# 2014_BALISE_CARTE_EMETTEUR.net
KiCad netlist of a schematic drawn in Altium Designer
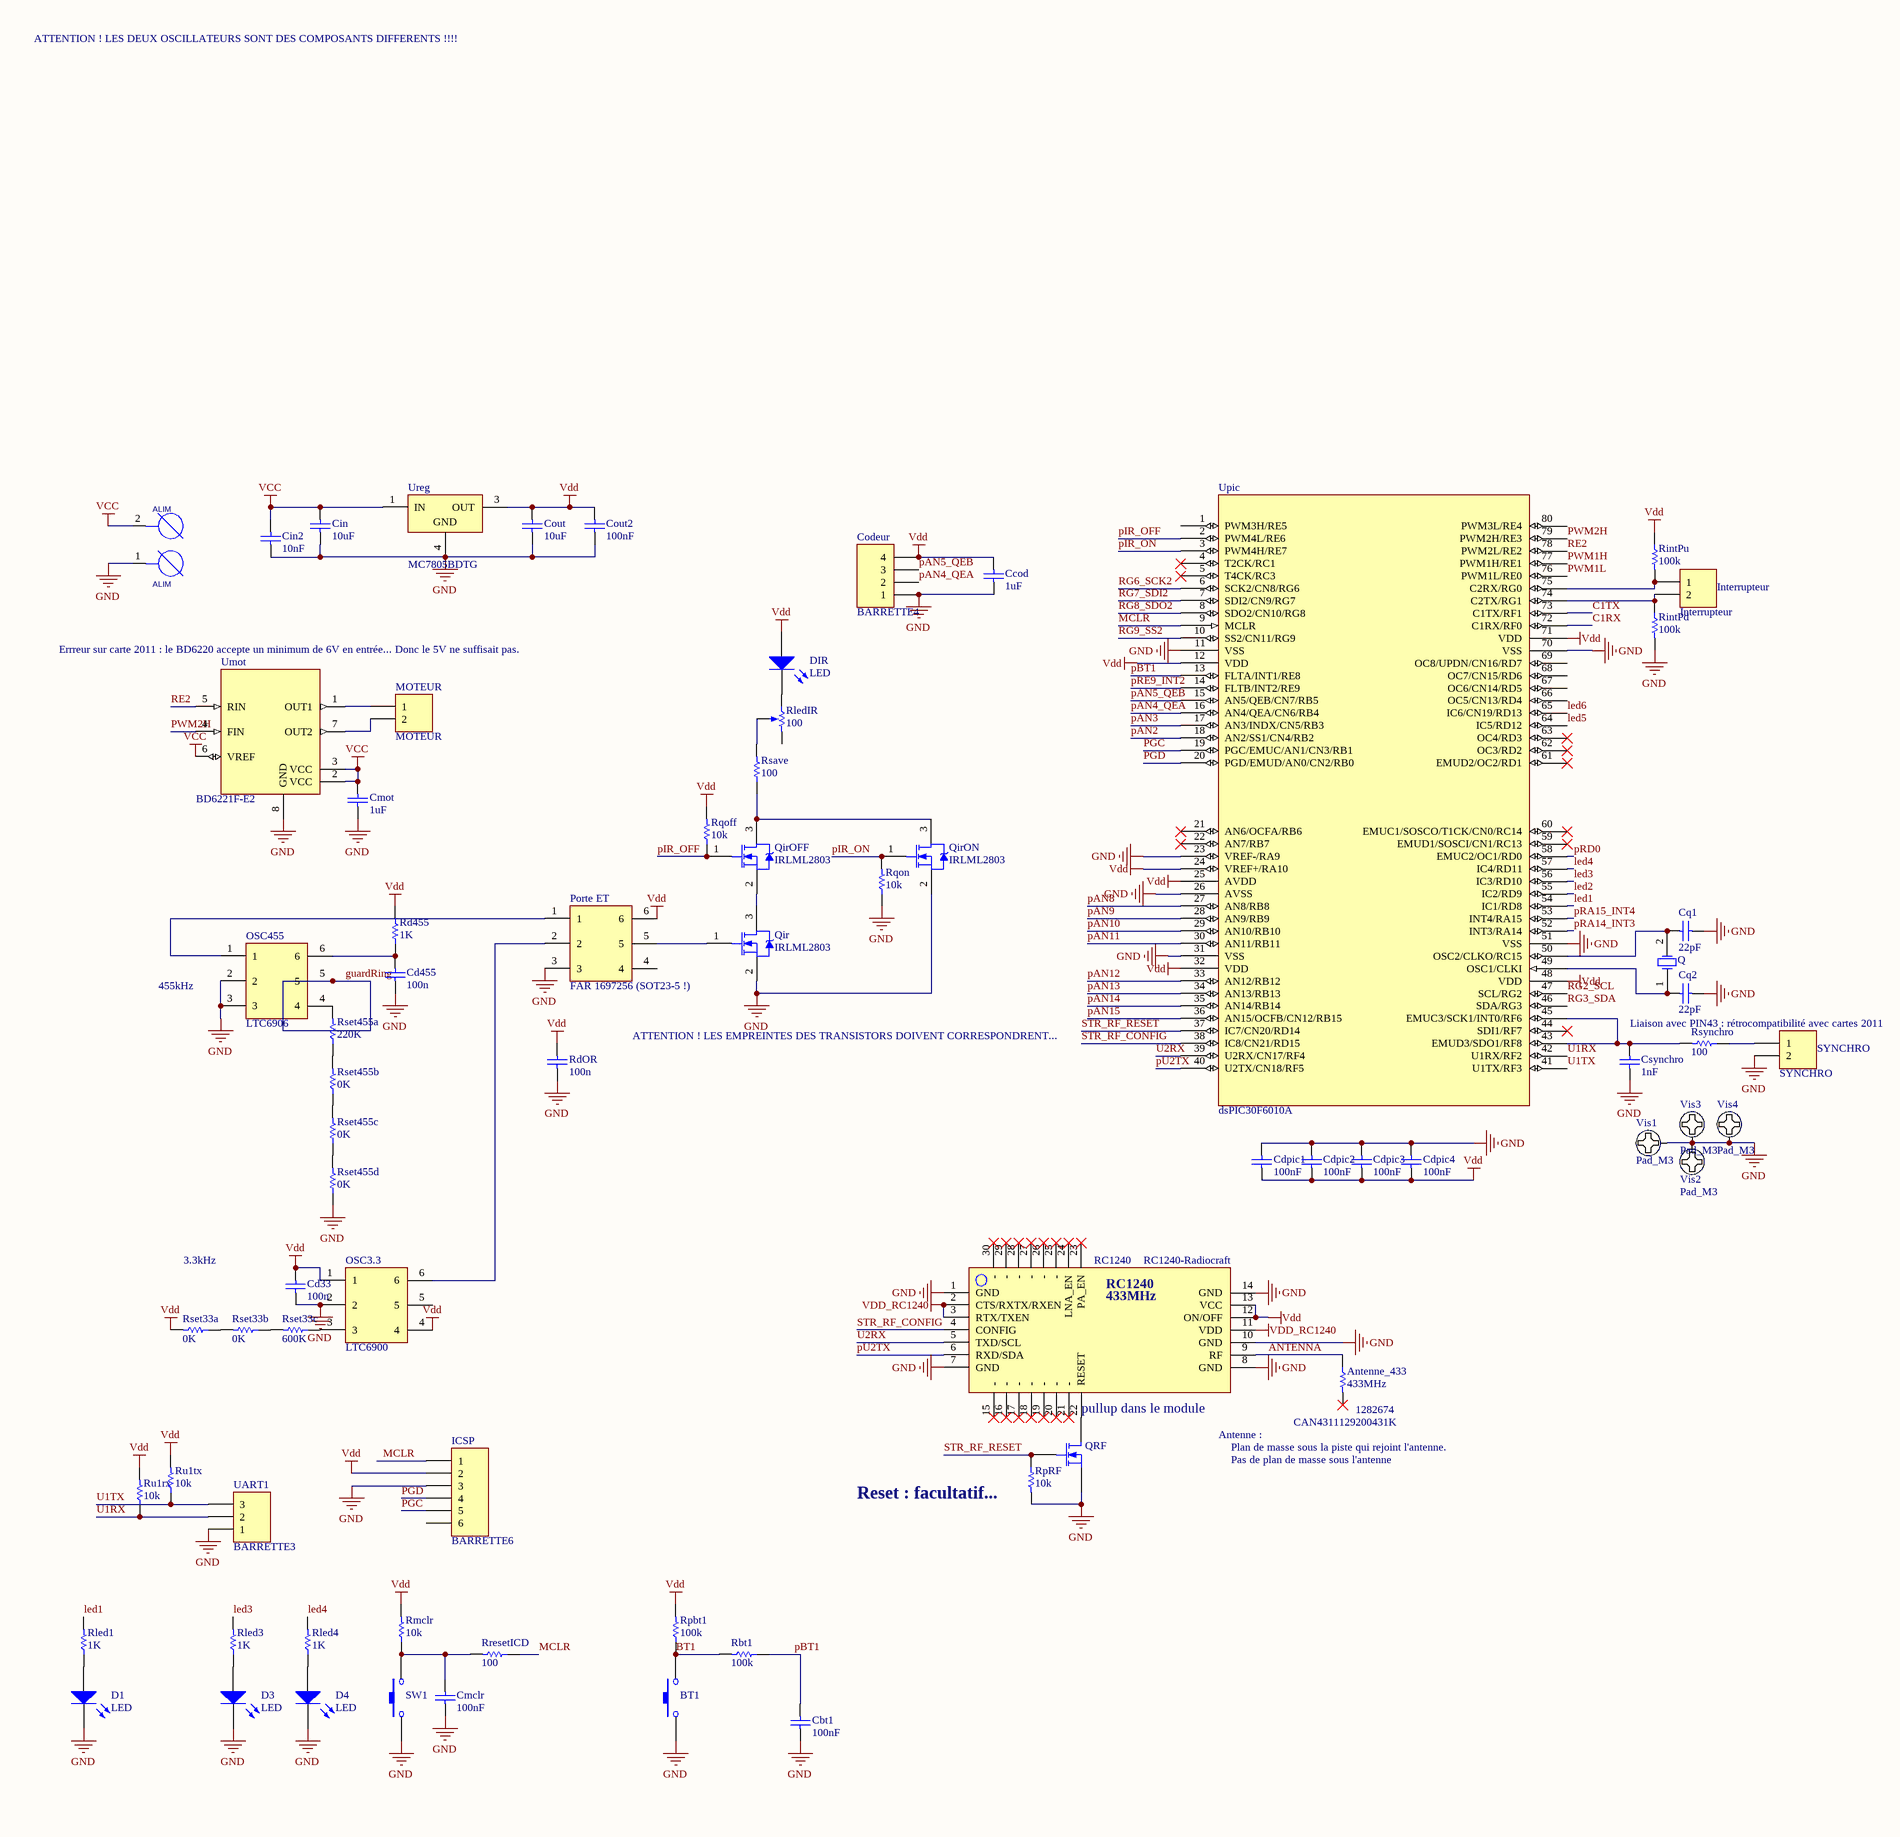
[diagram p0: 2014_BALISE_CARTE_EMETTEUR.SchDoc, left]
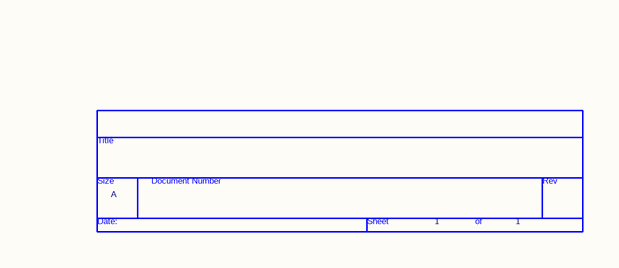
[diagram p1: 2014_BALISE_CARTE_EMETTEUR.SchDoc, right]

(export (version "E")
  (design (tool "Eeschema 10.0.6"))
  (components
    (comp (ref "*")
      (value "TitleBlock0")
      (fields (field (name "PAGE COUNT") "1") (field (name "PAGE NUMBER") "1") (field (name "PAGE SIZE") "A"))
      (libsource (lib "*") (part "TitleBlock0"))
    )
    (comp (ref "ALIM") (value "ALIM") (footprint "BORNIER2") (libsource (lib "*") (part "BORNIER2")))
    (comp (ref "Antenne_433")
      (value "433MHz")
      (footprint "R1206_N")
      (description "CAN4311129200431K")
      (fields
        (field (name "PACKAGEREFERENCE") "CAN4311129200431K")
        (field (name "FAR") "1282674")
        (field (name "PUBLISHER") "Altium Limited")
      )
      (libsource (lib "_ROBOT") (part "Resistor"))
    )
    (comp (ref "BT1")
      (value "SW_Pushbutton_6x6mm_Vertical")
      (footprint "Switch 6x6 Vertical")
      (description "Switch tactil 6mm x 6mm Vertical")
      (fields (field (name "PUBLISHER") "Damien Guitton"))
      (libsource (lib "DG_Interrupteur") (part "SW_Pushbutton_6x6mm_Vertical"))
    )
    (comp (ref "Cbt1")
      (value "100nF")
      (footprint "C0805_N")
      (description "Capacitor")
      (fields (field (name "PUBLISHER") "Altium Limited"))
      (libsource (lib "DG_Condensateur") (part "Capacitor"))
    )
    (comp (ref "Ccod")
      (value "1uF")
      (footprint "C1206_N")
      (description "Capacitor")
      (fields (field (name "PUBLISHER") "Altium Limited"))
      (libsource (lib "_ROBOT") (part "Condensateur"))
    )
    (comp (ref "Cd33")
      (value "100n")
      (footprint "C0805_N")
      (description "Capacitor")
      (fields (field (name "PUBLISHER") "Altium Limited"))
      (libsource (lib "_ROBOT") (part "Condensateur"))
    )
    (comp (ref "Cd455")
      (value "100n")
      (footprint "C0805_N")
      (description "Capacitor")
      (fields (field (name "PUBLISHER") "Altium Limited"))
      (libsource (lib "_ROBOT") (part "Condensateur"))
    )
    (comp (ref "Cdpic1")
      (value "100nF")
      (footprint "C0805_N")
      (description "Capacitor")
      (fields (field (name "PUBLISHER") "Altium Limited"))
      (libsource (lib "DG_Condensateur") (part "Capacitor"))
    )
    (comp (ref "Cdpic2")
      (value "100nF")
      (footprint "C0805_N")
      (description "Capacitor")
      (fields (field (name "PUBLISHER") "Altium Limited"))
      (libsource (lib "DG_Condensateur") (part "Capacitor"))
    )
    (comp (ref "Cdpic3")
      (value "100nF")
      (footprint "C0805_N")
      (description "Capacitor")
      (fields (field (name "PUBLISHER") "Altium Limited"))
      (libsource (lib "DG_Condensateur") (part "Capacitor"))
    )
    (comp (ref "Cdpic4")
      (value "100nF")
      (footprint "C0805_N")
      (description "Capacitor")
      (fields (field (name "PUBLISHER") "Altium Limited"))
      (libsource (lib "DG_Condensateur") (part "Capacitor"))
    )
    (comp (ref "Cin")
      (value "10uF")
      (footprint "C1206_N")
      (description "Capacitor")
      (fields (field (name "PUBLISHER") "Altium Limited"))
      (libsource (lib "DG_Condensateur") (part "Capacitor"))
    )
    (comp (ref "Cin2")
      (value "10nF")
      (footprint "C0805_N")
      (description "Capacitor")
      (fields (field (name "PUBLISHER") "Altium Limited"))
      (libsource (lib "DG_Condensateur") (part "Capacitor"))
    )
    (comp (ref "Cmclr")
      (value "100nF")
      (footprint "C0805_N")
      (description "Capacitor")
      (fields (field (name "PUBLISHER") "Altium Limited"))
      (libsource (lib "DG_Condensateur") (part "Capacitor"))
    )
    (comp (ref "Cmot")
      (value "1uF")
      (footprint "C1206_N")
      (description "Capacitor")
      (fields (field (name "PUBLISHER") "Altium Limited"))
      (libsource (lib "_ROBOT") (part "Condensateur"))
    )
    (comp (ref "Codeur")
      (value "BARRETTE4")
      (footprint "HE14_4")
      (description "Header, 4-Pin")
      (fields (field (name "PUBLISHER") "Altium Limited"))
      (libsource (lib "Connecteur") (part "BARRETTE4"))
    )
    (comp (ref "Cout")
      (value "10uF")
      (footprint "C1206_N")
      (description "Capacitor")
      (fields (field (name "PUBLISHER") "Altium Limited"))
      (libsource (lib "DG_Condensateur") (part "Capacitor"))
    )
    (comp (ref "Cout2")
      (value "100nF")
      (footprint "C0805_N")
      (description "Capacitor")
      (fields (field (name "PUBLISHER") "Altium Limited"))
      (libsource (lib "DG_Condensateur") (part "Capacitor"))
    )
    (comp (ref "Cq1")
      (value "22pF")
      (footprint "C0805_N")
      (description "Capacitor")
      (fields (field (name "PUBLISHER") "Altium Limited"))
      (libsource (lib "DG_Condensateur") (part "Capacitor"))
    )
    (comp (ref "Cq2")
      (value "22pF")
      (footprint "C0805_N")
      (description "Capacitor")
      (fields (field (name "PUBLISHER") "Altium Limited"))
      (libsource (lib "DG_Condensateur") (part "Capacitor"))
    )
    (comp (ref "Csynchro")
      (value "1nF")
      (footprint "C0805_N")
      (description "Capacitor")
      (fields (field (name "PUBLISHER") "Altium Limited"))
      (libsource (lib "DG_Condensateur") (part "Capacitor"))
    )
    (comp (ref "D1")
      (value "LED")
      (footprint "LED_0805")
      (description "Typical LED")
      (fields (field (name "PUBLISHER") "Altium Limited"))
      (libsource (lib "DG_LED") (part "LED"))
    )
    (comp (ref "D3")
      (value "LED")
      (footprint "LED_0805")
      (description "Typical LED")
      (fields (field (name "PUBLISHER") "Altium Limited"))
      (libsource (lib "DG_LED") (part "LED"))
    )
    (comp (ref "D4")
      (value "LED")
      (footprint "LED_0805")
      (description "Typical LED")
      (fields (field (name "PUBLISHER") "Altium Limited"))
      (libsource (lib "DG_LED") (part "LED"))
    )
    (comp (ref "DIR")
      (value "LED")
      (footprint "LED5")
      (description "Typical RED, GREEN, YELLOW, AMBER GaAs LED")
      (fields (field (name "PUBLISHER") "Altium Limited"))
      (libsource (lib "Robot2010") (part "LED"))
    )
    (comp (ref "ICSP")
      (value "BARRETTE6")
      (footprint "BARRETTE_6_M_C")
      (description "Header, 6-Pin")
      (fields (field (name "PUBLISHER") "Altium Limited"))
      (libsource (lib "Connecteur") (part "BARRETTE6"))
    )
    (comp (ref "Interrupteur")
      (value "Interrupteur")
      (footprint "Robot2010:HEADER2")
      (description "Header, 2-Pin")
      (fields (field (name "PUBLISHER") "Altium Limited"))
      (libsource (lib "Robot2010") (part "BARRETTE2"))
    )
    (comp (ref "MOTEUR")
      (value "MOTEUR")
      (footprint "Robot2010:HEADER2")
      (description "Header, 2-Pin")
      (fields (field (name "PUBLISHER") "Altium Limited"))
      (libsource (lib "Robot2010") (part "BARRETTE2"))
    )
    (comp (ref "OSC3.3")
      (value "LTC6900")
      (footprint "SOT23-6")
      (description "Header, 3-Pin, Dual row")
      (fields (field (name "PUBLISHER") "Altium Limited"))
      (libsource (lib "Robot2010") (part "SOT23-6"))
    )
    (comp (ref "OSC455")
      (value "LTC6906")
      (footprint "SOT23-6")
      (description "Header, 3-Pin, Dual row")
      (fields (field (name "PUBLISHER") "Altium Limited"))
      (libsource (lib "Robot2010") (part "SOT23-6"))
    )
    (comp (ref "Porte ET")
      (value "FAR 1697256 (SOT23-5 !)")
      (footprint "SOT23-6")
      (description "Header, 3-Pin, Dual row")
      (fields (field (name "PUBLISHER") "Altium Limited"))
      (libsource (lib "Robot2010") (part "SOT23-6"))
    )
    (comp (ref "Q")
      (value "QU")
      (footprint "HC49US")
      (description "Crystal Oscillator")
      (fields (field (name "PUBLISHER") "Altium Limited"))
      (libsource (lib "miniprojet") (part "QUARTZ_DROIT_BAS_PROFIL"))
    )
    (comp (ref "Qir")
      (value "IRLML2803")
      (footprint "SOT-23")
      (description "HEXFET Power MOSFET")
      (fields (field (name "PUBLISHER") "Altium Limited"))
      (libsource (lib "IR Discrete MOSFET - Power") (part "IRLML2803"))
    )
    (comp (ref "QirOFF")
      (value "IRLML2803")
      (footprint "SOT-23")
      (description "HEXFET Power MOSFET")
      (fields (field (name "PUBLISHER") "Altium Limited"))
      (libsource (lib "IR Discrete MOSFET - Power") (part "IRLML2803"))
    )
    (comp (ref "QirON")
      (value "IRLML2803")
      (footprint "SOT-23")
      (description "HEXFET Power MOSFET")
      (fields (field (name "PUBLISHER") "Altium Limited"))
      (libsource (lib "IR Discrete MOSFET - Power") (part "IRLML2803"))
    )
    (comp (ref "QRF")
      (value "Transistor MOSFET-N")
      (footprint "SOT23-3N")
      (description "N-Channel MOSFET")
      (fields (field (name "PUBLISHER") "Altium Limited"))
      (libsource (lib "_ROBOT") (part "Transistor MOSFET-N"))
    )
    (comp (ref "Rbt1")
      (value "100k")
      (footprint "R1206_N")
      (description "Resistor")
      (fields (field (name "PUBLISHER") "Altium Limited"))
      (libsource (lib "DG_Resistance") (part "Resistor"))
    )
    (comp (ref "RC1240")
      (value "RC1240-Radiocraft")
      (footprint "RC1240")
      (description "RC1240 - Radiocraft 433MHz Transceiver")
      (libsource (lib "_ROBOT") (part "RC1240-Radiocraft"))
    )
    (comp (ref "Rd455")
      (value "1K")
      (footprint "R1206_N")
      (description "Resistor")
      (fields (field (name "PUBLISHER") "Altium Limited"))
      (libsource (lib "_ROBOT") (part "Resistor"))
    )
    (comp (ref "RdOR")
      (value "100n")
      (footprint "C0805_N")
      (description "Capacitor")
      (fields (field (name "PUBLISHER") "Altium Limited"))
      (libsource (lib "_ROBOT") (part "Condensateur"))
    )
    (comp (ref "RintPd")
      (value "100k")
      (footprint "R1206_N")
      (description "Resistor")
      (fields (field (name "PUBLISHER") "Altium Limited"))
      (libsource (lib "_ROBOT") (part "Resistor"))
    )
    (comp (ref "RintPu")
      (value "100k")
      (footprint "R1206_N")
      (description "Resistor")
      (fields (field (name "PUBLISHER") "Altium Limited"))
      (libsource (lib "_ROBOT") (part "Resistor"))
    )
    (comp (ref "Rled1")
      (value "1K")
      (footprint "R1206_N")
      (description "Resistor")
      (fields (field (name "PUBLISHER") "Altium Limited"))
      (libsource (lib "DG_Resistance") (part "Resistor"))
    )
    (comp (ref "Rled3")
      (value "1K")
      (footprint "R1206_N")
      (description "Resistor")
      (fields (field (name "PUBLISHER") "Altium Limited"))
      (libsource (lib "DG_Resistance") (part "Resistor"))
    )
    (comp (ref "Rled4")
      (value "1K")
      (footprint "R1206_N")
      (description "Resistor")
      (fields (field (name "PUBLISHER") "Altium Limited"))
      (libsource (lib "DG_Resistance") (part "Resistor"))
    )
    (comp (ref "RledIR")
      (value "100")
      (footprint "Trimmer_Bourns_3314G")
      (description "Trimmer monotour, Bourns,serie 3314P")
      (libsource (lib "DG_Resistance") (part "Trimmer monotour, Bourns,serie 3314P"))
    )
    (comp (ref "Rmclr")
      (value "10k")
      (footprint "R1206_N")
      (description "Resistor")
      (fields (field (name "PUBLISHER") "Altium Limited"))
      (libsource (lib "DG_Resistance") (part "Resistor"))
    )
    (comp (ref "Rpbt1")
      (value "100k")
      (footprint "R1206_N")
      (description "Resistor")
      (fields (field (name "PUBLISHER") "Altium Limited"))
      (libsource (lib "DG_Resistance") (part "Resistor"))
    )
    (comp (ref "RpRF")
      (value "10k")
      (footprint "R1206_N")
      (description "Resistor")
      (fields (field (name "PUBLISHER") "Altium Limited"))
      (libsource (lib "_ROBOT") (part "Resistor"))
    )
    (comp (ref "Rqoff")
      (value "10k")
      (footprint "R1206_N")
      (description "Resistor")
      (fields (field (name "PUBLISHER") "Altium Limited"))
      (libsource (lib "_ROBOT") (part "Resistor"))
    )
    (comp (ref "Rqon")
      (value "10k")
      (footprint "R1206_N")
      (description "Resistor")
      (fields (field (name "PUBLISHER") "Altium Limited"))
      (libsource (lib "_ROBOT") (part "Resistor"))
    )
    (comp (ref "RresetICD")
      (value "100")
      (footprint "R1206_N")
      (description "Resistor")
      (fields (field (name "PUBLISHER") "Altium Limited"))
      (libsource (lib "DG_Resistance") (part "Resistor"))
    )
    (comp (ref "Rsave")
      (value "100")
      (footprint "R1206_N")
      (description "Resistor")
      (fields (field (name "PUBLISHER") "Altium Limited"))
      (libsource (lib "_ROBOT") (part "Resistor"))
    )
    (comp (ref "Rset33a")
      (value "0K")
      (footprint "R1206_N")
      (description "Resistor")
      (fields (field (name "PUBLISHER") "Altium Limited"))
      (libsource (lib "_ROBOT") (part "Resistor"))
    )
    (comp (ref "Rset33b")
      (value "0K")
      (footprint "R1206_N")
      (description "Resistor")
      (fields (field (name "PUBLISHER") "Altium Limited"))
      (libsource (lib "_ROBOT") (part "Resistor"))
    )
    (comp (ref "Rset33c")
      (value "600K")
      (footprint "R1206_N")
      (description "Resistor")
      (fields (field (name "PUBLISHER") "Altium Limited"))
      (libsource (lib "_ROBOT") (part "Resistor"))
    )
    (comp (ref "Rset455a")
      (value "220K")
      (footprint "R1206_N")
      (description "Resistor")
      (fields (field (name "PUBLISHER") "Altium Limited"))
      (libsource (lib "_ROBOT") (part "Resistor"))
    )
    (comp (ref "Rset455b")
      (value "0K")
      (footprint "R1206_N")
      (description "Resistor")
      (fields (field (name "PUBLISHER") "Altium Limited"))
      (libsource (lib "_ROBOT") (part "Resistor"))
    )
    (comp (ref "Rset455c")
      (value "0K")
      (footprint "R1206_N")
      (description "Resistor")
      (fields (field (name "PUBLISHER") "Altium Limited"))
      (libsource (lib "_ROBOT") (part "Resistor"))
    )
    (comp (ref "Rset455d")
      (value "0K")
      (footprint "R1206_N")
      (description "Resistor")
      (fields (field (name "PUBLISHER") "Altium Limited"))
      (libsource (lib "_ROBOT") (part "Resistor"))
    )
    (comp (ref "Rsynchro")
      (value "100")
      (footprint "R1206_N")
      (description "Resistor")
      (fields (field (name "PUBLISHER") "Altium Limited"))
      (libsource (lib "_ROBOT") (part "Resistor"))
    )
    (comp (ref "Ru1rx")
      (value "10k")
      (footprint "R1206_N")
      (description "Resistor")
      (fields (field (name "PUBLISHER") "Altium Limited"))
      (libsource (lib "DG_Resistance") (part "Resistor"))
    )
    (comp (ref "Ru1tx")
      (value "10k")
      (footprint "R1206_N")
      (description "Resistor")
      (fields (field (name "PUBLISHER") "Altium Limited"))
      (libsource (lib "DG_Resistance") (part "Resistor"))
    )
    (comp (ref "SW1")
      (value "SW_Pushbutton_6x6mm_Vertical")
      (footprint "Switch 6x6 Vertical")
      (description "Switch tactil 6mm x 6mm Vertical")
      (fields (field (name "PUBLISHER") "Damien Guitton"))
      (libsource (lib "DG_Interrupteur") (part "SW_Pushbutton_6x6mm_Vertical"))
    )
    (comp (ref "SYNCHRO")
      (value "SYNCHRO")
      (footprint "Robot2010:HEADER2")
      (description "Header, 2-Pin")
      (fields (field (name "PUBLISHER") "Altium Limited"))
      (libsource (lib "Robot2010") (part "BARRETTE2"))
    )
    (comp (ref "UART1")
      (value "BARRETTE3")
      (footprint "BARRETTE_3_M_C")
      (description "Header, 3-Pin")
      (fields (field (name "PUBLISHER") "Altium Limited"))
      (libsource (lib "Connecteur") (part "BARRETTE3"))
    )
    (comp (ref "Umot")
      (value "BD6221F-E2")
      (footprint "SO8_N")
      (description "H Bridge - 2A")
      (libsource (lib "Circuit intégré") (part "BD6220F"))
    )
    (comp (ref "Upic")
      (value "dsPIC30F6010A")
      (footprint "TQFP80_N")
      (description "High-Performance, 16-bit Digital Signal Controllers")
      (libsource (lib "DG_Microcontroleur") (part "dsPIC30F6010A"))
    )
    (comp (ref "Ureg")
      (value "MC7805BDTG")
      (footprint "369A-13")
      (description "Three-Terminal Positive Voltage Regulator")
      (fields (field (name "PUBLISHER") "Altium Limited"))
      (libsource (lib "ON Semi Power Mgt Voltage Regulator") (part "MC7805ACD2T"))
    )
    (comp (ref "Vis1")
      (value "Pad_M3")
      (footprint "M3x6mm")
      (description "Vis M3 X 6mm _TORX_Tête 6mm")
      (fields (field (name "PUBLISHER") "Damien Guitton"))
      (libsource (lib "DG_Mecanique") (part "Vis M3 X 6mm _TORX_Tête 6mm"))
    )
    (comp (ref "Vis2")
      (value "Pad_M3")
      (footprint "M3x6mm")
      (description "Vis M3 X 6mm _TORX_Tête 6mm")
      (fields (field (name "PUBLISHER") "Damien Guitton"))
      (libsource (lib "DG_Mecanique") (part "Vis M3 X 6mm _TORX_Tête 6mm"))
    )
    (comp (ref "Vis3")
      (value "Pad_M3")
      (footprint "M3x6mm")
      (description "Vis M3 X 6mm _TORX_Tête 6mm")
      (fields (field (name "PUBLISHER") "Damien Guitton"))
      (libsource (lib "DG_Mecanique") (part "Vis M3 X 6mm _TORX_Tête 6mm"))
    )
    (comp (ref "Vis4")
      (value "Pad_M3")
      (footprint "M3x6mm")
      (description "Vis M3 X 6mm _TORX_Tête 6mm")
      (fields (field (name "PUBLISHER") "Damien Guitton"))
      (libsource (lib "DG_Mecanique") (part "Vis M3 X 6mm _TORX_Tête 6mm"))
    )
  )
  (nets
    (net (code "1") (name "/ANTENNA") (class "Default")
      (node (ref "Antenne_433") (pin "1") (pinfunction "1_1") (pintype "passive"))
      (node (ref "RC1240") (pin "9") (pinfunction "RF_9") (pintype "passive"))
    )
    (net (code "2") (name "/BT1") (class "Default")
      (node (ref "BT1") (pin "3") (pinfunction "3_3") (pintype "passive"))
      (node (ref "Rbt1") (pin "2") (pinfunction "2_2") (pintype "passive"))
      (node (ref "Rpbt1") (pin "1") (pinfunction "1_1") (pintype "passive"))
    )
    (net (code "3") (name "/C1RX") (class "Default")
      (node (ref "Upic") (pin "72") (pinfunction "C1RX/RF0_72") (pintype "bidirectional"))
    )
    (net (code "4") (name "/C1TX") (class "Default")
      (node (ref "Upic") (pin "73") (pinfunction "C1TX/RF1_73") (pintype "bidirectional"))
    )
    (net (code "5") (name "/MCLR") (class "Default")
      (node (ref "ICSP") (pin "1") (pinfunction "1_1") (pintype "passive"))
      (node (ref "RresetICD") (pin "1") (pinfunction "1_1") (pintype "passive"))
      (node (ref "Upic") (pin "9") (pinfunction "MCLR_9") (pintype "input"))
    )
    (net (code "6") (name "/PGC") (class "Default")
      (node (ref "ICSP") (pin "5") (pinfunction "5_5") (pintype "passive"))
      (node (ref "Upic") (pin "19") (pinfunction "PGC/EMUC/AN1/CN3/RB1_19") (pintype "bidirectional"))
    )
    (net (code "7") (name "/PGD") (class "Default")
      (node (ref "ICSP") (pin "4") (pinfunction "4_4") (pintype "passive"))
      (node (ref "Upic") (pin "20") (pinfunction "PGD/EMUD/AN0/CN2/RB0_20") (pintype "bidirectional"))
    )
    (net (code "8") (name "/PWM1H") (class "Default")
      (node (ref "Upic") (pin "77") (pinfunction "PWM1H/RE1_77") (pintype "bidirectional"))
    )
    (net (code "9") (name "/PWM1L") (class "Default")
      (node (ref "Upic") (pin "76") (pinfunction "PWM1L/RE0_76") (pintype "bidirectional"))
    )
    (net (code "10") (name "/PWM2H") (class "Default")
      (node (ref "Umot") (pin "4") (pinfunction "FIN_4") (pintype "input"))
      (node (ref "Upic") (pin "79") (pinfunction "PWM2H/RE3_79") (pintype "bidirectional"))
    )
    (net (code "11") (name "/RE2") (class "Default")
      (node (ref "Umot") (pin "5") (pinfunction "RIN_5") (pintype "input"))
      (node (ref "Upic") (pin "78") (pinfunction "PWM2L/RE2_78") (pintype "bidirectional"))
    )
    (net (code "12") (name "/RG2_SCL") (class "Default")
      (node (ref "Upic") (pin "47") (pinfunction "SCL/RG2_47") (pintype "bidirectional"))
    )
    (net (code "13") (name "/RG3_SDA") (class "Default")
      (node (ref "Upic") (pin "46") (pinfunction "SDA/RG3_46") (pintype "bidirectional"))
    )
    (net (code "14") (name "/RG6_SCK2") (class "Default")
      (node (ref "Upic") (pin "6") (pinfunction "SCK2/CN8/RG6_6") (pintype "bidirectional"))
    )
    (net (code "15") (name "/RG7_SDI2") (class "Default")
      (node (ref "Upic") (pin "7") (pinfunction "SDI2/CN9/RG7_7") (pintype "bidirectional"))
    )
    (net (code "16") (name "/RG8_SDO2") (class "Default")
      (node (ref "Upic") (pin "8") (pinfunction "SDO2/CN10/RG8_8") (pintype "bidirectional"))
    )
    (net (code "17") (name "/RG9_SS2") (class "Default")
      (node (ref "Upic") (pin "10") (pinfunction "SS2/CN11/RG9_10") (pintype "bidirectional"))
    )
    (net (code "18") (name "/STR_RF_CONFIG") (class "Default")
      (node (ref "RC1240") (pin "4") (pinfunction "CONFIG_4") (pintype "passive"))
      (node (ref "Upic") (pin "38") (pinfunction "IC8/CN21/RD15_38") (pintype "bidirectional"))
    )
    (net (code "19") (name "/STR_RF_RESET") (class "Default")
      (node (ref "QRF") (pin "1") (pinfunction "G_1") (pintype "passive"))
      (node (ref "RpRF") (pin "1") (pinfunction "1_1") (pintype "passive"))
      (node (ref "Upic") (pin "37") (pinfunction "IC7/CN20/RD14_37") (pintype "bidirectional"))
    )
    (net (code "20") (name "/U1RX") (class "Default")
      (node (ref "Ru1rx") (pin "1") (pinfunction "1_1") (pintype "passive"))
      (node (ref "UART1") (pin "2") (pinfunction "2_2") (pintype "passive"))
      (node (ref "Upic") (pin "42") (pinfunction "U1RX/RF2_42") (pintype "bidirectional"))
    )
    (net (code "21") (name "/U1TX") (class "Default")
      (node (ref "Ru1tx") (pin "1") (pinfunction "1_1") (pintype "passive"))
      (node (ref "UART1") (pin "3") (pinfunction "3_3") (pintype "passive"))
      (node (ref "Upic") (pin "41") (pinfunction "U1TX/RF3_41") (pintype "bidirectional"))
    )
    (net (code "22") (name "/U2RX") (class "Default")
      (node (ref "RC1240") (pin "5") (pinfunction "TXD/SCL_5") (pintype "passive"))
      (node (ref "Upic") (pin "39") (pinfunction "U2RX/CN17/RF4_39") (pintype "bidirectional"))
    )
    (net (code "23") (name "/guardRing") (class "Default")
      (node (ref "OSC455") (pin "5") (pinfunction "5_5") (pintype "passive"))
    )
    (net (code "24") (name "/led1") (class "Default")
      (node (ref "Rled1") (pin "2") (pinfunction "2_2") (pintype "passive"))
      (node (ref "Upic") (pin "54") (pinfunction "IC1/RD8_54") (pintype "bidirectional"))
    )
    (net (code "25") (name "/led2") (class "Default")
      (node (ref "Upic") (pin "55") (pinfunction "IC2/RD9_55") (pintype "bidirectional"))
    )
    (net (code "26") (name "/led3") (class "Default")
      (node (ref "Rled3") (pin "2") (pinfunction "2_2") (pintype "passive"))
      (node (ref "Upic") (pin "56") (pinfunction "IC3/RD10_56") (pintype "bidirectional"))
    )
    (net (code "27") (name "/led4") (class "Default")
      (node (ref "Rled4") (pin "2") (pinfunction "2_2") (pintype "passive"))
      (node (ref "Upic") (pin "57") (pinfunction "IC4/RD11_57") (pintype "bidirectional"))
    )
    (net (code "28") (name "/led5") (class "Default")
      (node (ref "Upic") (pin "64") (pinfunction "IC5/RD12_64") (pintype "bidirectional"))
    )
    (net (code "29") (name "/led6") (class "Default")
      (node (ref "Upic") (pin "65") (pinfunction "IC6/CN19/RD13_65") (pintype "bidirectional"))
    )
    (net (code "30") (name "/pAN2") (class "Default")
      (node (ref "Upic") (pin "18") (pinfunction "AN2/SS1/CN4/RB2_18") (pintype "bidirectional"))
    )
    (net (code "31") (name "/pAN3") (class "Default")
      (node (ref "Upic") (pin "17") (pinfunction "AN3/INDX/CN5/RB3_17") (pintype "bidirectional"))
    )
    (net (code "32") (name "/pAN4_QEA") (class "Default")
      (node (ref "Codeur") (pin "2") (pinfunction "2_2") (pintype "passive"))
      (node (ref "Upic") (pin "16") (pinfunction "AN4/QEA/CN6/RB4_16") (pintype "bidirectional"))
    )
    (net (code "33") (name "/pAN5_QEB") (class "Default")
      (node (ref "Codeur") (pin "3") (pinfunction "3_3") (pintype "passive"))
      (node (ref "Upic") (pin "15") (pinfunction "AN5/QEB/CN7/RB5_15") (pintype "bidirectional"))
    )
    (net (code "34") (name "/pAN8") (class "Default")
      (node (ref "Upic") (pin "27") (pinfunction "AN8/RB8_27") (pintype "bidirectional"))
    )
    (net (code "35") (name "/pAN9") (class "Default")
      (node (ref "Upic") (pin "28") (pinfunction "AN9/RB9_28") (pintype "bidirectional"))
    )
    (net (code "36") (name "/pAN10") (class "Default")
      (node (ref "Upic") (pin "29") (pinfunction "AN10/RB10_29") (pintype "bidirectional"))
    )
    (net (code "37") (name "/pAN11") (class "Default")
      (node (ref "Upic") (pin "30") (pinfunction "AN11/RB11_30") (pintype "bidirectional"))
    )
    (net (code "38") (name "/pAN12") (class "Default")
      (node (ref "Upic") (pin "33") (pinfunction "AN12/RB12_33") (pintype "bidirectional"))
    )
    (net (code "39") (name "/pAN13") (class "Default")
      (node (ref "Upic") (pin "34") (pinfunction "AN13/RB13_34") (pintype "bidirectional"))
    )
    (net (code "40") (name "/pAN14") (class "Default")
      (node (ref "Upic") (pin "35") (pinfunction "AN14/RB14_35") (pintype "bidirectional"))
    )
    (net (code "41") (name "/pAN15") (class "Default")
      (node (ref "Upic") (pin "36") (pinfunction "AN15/OCFB/CN12/RB15_36") (pintype "bidirectional"))
    )
    (net (code "42") (name "/pBT1") (class "Default")
      (node (ref "Cbt1") (pin "2") (pinfunction "2_2") (pintype "passive"))
      (node (ref "Rbt1") (pin "1") (pinfunction "1_1") (pintype "passive"))
      (node (ref "Upic") (pin "13") (pinfunction "FLTA/INT1/RE8_13") (pintype "bidirectional"))
    )
    (net (code "43") (name "/pIR_OFF") (class "Default")
      (node (ref "QirOFF") (pin "1") (pinfunction "G_1") (pintype "passive"))
      (node (ref "Rqoff") (pin "1") (pinfunction "1_1") (pintype "passive"))
      (node (ref "Upic") (pin "2") (pinfunction "PWM4L/RE6_2") (pintype "bidirectional"))
    )
    (net (code "44") (name "/pIR_ON") (class "Default")
      (node (ref "QirON") (pin "1") (pinfunction "G_1") (pintype "passive"))
      (node (ref "Rqon") (pin "2") (pinfunction "2_2") (pintype "passive"))
      (node (ref "Upic") (pin "3") (pinfunction "PWM4H/RE7_3") (pintype "bidirectional"))
    )
    (net (code "45") (name "/pRA14_INT3") (class "Default")
      (node (ref "Upic") (pin "52") (pinfunction "INT3/RA14_52") (pintype "bidirectional"))
    )
    (net (code "46") (name "/pRA15_INT4") (class "Default")
      (node (ref "Upic") (pin "53") (pinfunction "INT4/RA15_53") (pintype "bidirectional"))
    )
    (net (code "47") (name "/pRD0") (class "Default")
      (node (ref "Upic") (pin "58") (pinfunction "EMUC2/OC1/RD0_58") (pintype "bidirectional"))
    )
    (net (code "48") (name "/pRE9_INT2") (class "Default")
      (node (ref "Upic") (pin "14") (pinfunction "FLTB/INT2/RE9_14") (pintype "bidirectional"))
    )
    (net (code "49") (name "/pU2TX") (class "Default")
      (node (ref "RC1240") (pin "6") (pinfunction "RXD/SDA_6") (pintype "passive"))
      (node (ref "Upic") (pin "40") (pinfunction "U2TX/CN18/RF5_40") (pintype "bidirectional"))
    )
    (net (code "50") (name "GND") (class "Default")
      (node (ref "ALIM") (pin "1") (pinfunction "B1_1") (pintype "passive"))
      (node (ref "BT1") (pin "1") (pinfunction "1_1") (pintype "passive"))
      (node (ref "Cbt1") (pin "1") (pinfunction "1_1") (pintype "passive"))
      (node (ref "Ccod") (pin "1") (pinfunction "1_1") (pintype "passive"))
      (node (ref "Cd33") (pin "1") (pinfunction "1_1") (pintype "passive"))
      (node (ref "Cd455") (pin "1") (pinfunction "1_1") (pintype "passive"))
      (node (ref "Cdpic1") (pin "2") (pinfunction "2_2") (pintype "passive"))
      (node (ref "Cdpic2") (pin "2") (pinfunction "2_2") (pintype "passive"))
      (node (ref "Cdpic3") (pin "2") (pinfunction "2_2") (pintype "passive"))
      (node (ref "Cdpic4") (pin "2") (pinfunction "2_2") (pintype "passive"))
      (node (ref "Cin") (pin "1") (pinfunction "1_1") (pintype "passive"))
      (node (ref "Cin2") (pin "1") (pinfunction "1_1") (pintype "passive"))
      (node (ref "Cmclr") (pin "1") (pinfunction "1_1") (pintype "passive"))
      (node (ref "Cmot") (pin "1") (pinfunction "1_1") (pintype "passive"))
      (node (ref "Codeur") (pin "1") (pinfunction "1_1") (pintype "passive"))
      (node (ref "Cout") (pin "1") (pinfunction "1_1") (pintype "passive"))
      (node (ref "Cout2") (pin "1") (pinfunction "1_1") (pintype "passive"))
      (node (ref "Cq1") (pin "2") (pinfunction "2_2") (pintype "passive"))
      (node (ref "Cq2") (pin "2") (pinfunction "2_2") (pintype "passive"))
      (node (ref "Csynchro") (pin "1") (pinfunction "1_1") (pintype "passive"))
      (node (ref "D1") (pin "2") (pinfunction "2_2") (pintype "passive"))
      (node (ref "D3") (pin "2") (pinfunction "2_2") (pintype "passive"))
      (node (ref "D4") (pin "2") (pinfunction "2_2") (pintype "passive"))
      (node (ref "ICSP") (pin "3") (pinfunction "3_3") (pintype "passive"))
      (node (ref "OSC3.3") (pin "2") (pinfunction "2_2") (pintype "passive"))
      (node (ref "OSC455") (pin "2") (pinfunction "2_2") (pintype "passive"))
      (node (ref "OSC455") (pin "3") (pinfunction "3_3") (pintype "passive"))
      (node (ref "Porte ET") (pin "3") (pinfunction "3_3") (pintype "passive"))
      (node (ref "QRF") (pin "2") (pinfunction "S_2") (pintype "passive"))
      (node (ref "Qir") (pin "2") (pinfunction "S_2") (pintype "passive"))
      (node (ref "QirON") (pin "2") (pinfunction "S_2") (pintype "passive"))
      (node (ref "RC1240") (pin "1") (pinfunction "GND_1") (pintype "passive"))
      (node (ref "RC1240") (pin "10") (pinfunction "GND_10") (pintype "passive"))
      (node (ref "RC1240") (pin "14") (pinfunction "GND_14") (pintype "passive"))
      (node (ref "RC1240") (pin "7") (pinfunction "GND_7") (pintype "passive"))
      (node (ref "RC1240") (pin "8") (pinfunction "GND_8") (pintype "passive"))
      (node (ref "RdOR") (pin "1") (pinfunction "1_1") (pintype "passive"))
      (node (ref "RintPd") (pin "2") (pinfunction "2_2") (pintype "passive"))
      (node (ref "RpRF") (pin "2") (pinfunction "2_2") (pintype "passive"))
      (node (ref "Rqon") (pin "1") (pinfunction "1_1") (pintype "passive"))
      (node (ref "Rset455d") (pin "1") (pinfunction "1_1") (pintype "passive"))
      (node (ref "SW1") (pin "1") (pinfunction "1_1") (pintype "passive"))
      (node (ref "SYNCHRO") (pin "2") (pinfunction "2_2") (pintype "passive"))
      (node (ref "UART1") (pin "1") (pinfunction "1_1") (pintype "passive"))
      (node (ref "Umot") (pin "8") (pinfunction "GND_8") (pintype "power_in"))
      (node (ref "Upic") (pin "11") (pinfunction "VSS_11") (pintype "power_in"))
      (node (ref "Upic") (pin "23") (pinfunction "VREF-/RA9_23") (pintype "bidirectional"))
      (node (ref "Upic") (pin "26") (pinfunction "AVSS_26") (pintype "power_in"))
      (node (ref "Upic") (pin "31") (pinfunction "VSS_31") (pintype "power_in"))
      (node (ref "Upic") (pin "51") (pinfunction "VSS_51") (pintype "power_in"))
      (node (ref "Upic") (pin "70") (pinfunction "VSS_70") (pintype "power_in"))
      (node (ref "Ureg") (pin "4") (pinfunction "GND_4") (pintype "power_in"))
      (node (ref "Vis1") (pin "1") (pinfunction "1_1") (pintype "passive"))
      (node (ref "Vis2") (pin "1") (pinfunction "1_1") (pintype "passive"))
      (node (ref "Vis3") (pin "1") (pinfunction "1_1") (pintype "passive"))
      (node (ref "Vis4") (pin "1") (pinfunction "1_1") (pintype "passive"))
    )
    (net (code "51") (name "Net-(Cd455-Pad2)") (class "Default")
      (node (ref "Cd455") (pin "2") (pinfunction "2_2") (pintype "passive"))
      (node (ref "OSC455") (pin "6") (pinfunction "6_6") (pintype "passive"))
      (node (ref "Rd455") (pin "1") (pinfunction "1_1") (pintype "passive"))
    )
    (net (code "52") (name "Net-(Cmclr-Pad2)") (class "Default")
      (node (ref "Cmclr") (pin "2") (pinfunction "2_2") (pintype "passive"))
      (node (ref "Rmclr") (pin "1") (pinfunction "1_1") (pintype "passive"))
      (node (ref "RresetICD") (pin "2") (pinfunction "2_2") (pintype "passive"))
      (node (ref "SW1") (pin "3") (pinfunction "3_3") (pintype "passive"))
    )
    (net (code "53") (name "Net-(D1-Pad1)") (class "Default")
      (node (ref "D1") (pin "1") (pinfunction "1_1") (pintype "passive"))
      (node (ref "Rled1") (pin "1") (pinfunction "1_1") (pintype "passive"))
    )
    (net (code "54") (name "Net-(D3-Pad1)") (class "Default")
      (node (ref "D3") (pin "1") (pinfunction "1_1") (pintype "passive"))
      (node (ref "Rled3") (pin "1") (pinfunction "1_1") (pintype "passive"))
    )
    (net (code "55") (name "Net-(D4-Pad1)") (class "Default")
      (node (ref "D4") (pin "1") (pinfunction "1_1") (pintype "passive"))
      (node (ref "Rled4") (pin "1") (pinfunction "1_1") (pintype "passive"))
    )
    (net (code "56") (name "Net-(OSC3.3-Pad3)") (class "Default")
      (node (ref "OSC3.3") (pin "3") (pinfunction "3_3") (pintype "passive"))
      (node (ref "Rset33c") (pin "1") (pinfunction "1_1") (pintype "passive"))
    )
    (net (code "57") (name "Net-(OSC3.3-Pad6)") (class "Default")
      (node (ref "OSC3.3") (pin "6") (pinfunction "6_6") (pintype "passive"))
      (node (ref "Porte ET") (pin "2") (pinfunction "2_2") (pintype "passive"))
    )
    (net (code "58") (name "Net-(OSC455-Pad1)") (class "Default")
      (node (ref "OSC455") (pin "1") (pinfunction "1_1") (pintype "passive"))
      (node (ref "Porte ET") (pin "1") (pinfunction "1_1") (pintype "passive"))
    )
    (net (code "59") (name "Net-(OSC455-Pad4)") (class "Default")
      (node (ref "OSC455") (pin "4") (pinfunction "4_4") (pintype "passive"))
      (node (ref "Rset455a") (pin "2") (pinfunction "2_2") (pintype "passive"))
    )
    (net (code "60") (name "Net-(Q-OSC1)") (class "Default")
      (node (ref "Cq2") (pin "1") (pinfunction "1_1") (pintype "passive"))
      (node (ref "Q") (pin "1") (pinfunction "OSC1_1") (pintype "passive"))
      (node (ref "Upic") (pin "49") (pinfunction "OSC1/CLKI_49") (pintype "input"))
    )
    (net (code "61") (name "Net-(Q-OSC2)") (class "Default")
      (node (ref "Cq1") (pin "1") (pinfunction "1_1") (pintype "passive"))
      (node (ref "Q") (pin "2") (pinfunction "OSC2_2") (pintype "passive"))
      (node (ref "Upic") (pin "50") (pinfunction "OSC2/CLKO/RC15_50") (pintype "bidirectional"))
    )
    (net (code "62") (name "Net-(QRF-D)") (class "Default")
      (node (ref "QRF") (pin "3") (pinfunction "D_3") (pintype "passive"))
      (node (ref "RC1240") (pin "22") (pinfunction "RESET_22") (pintype "passive"))
    )
    (net (code "63") (name "Net-(Qir-D)") (class "Default")
      (node (ref "Qir") (pin "3") (pinfunction "D_3") (pintype "passive"))
      (node (ref "QirOFF") (pin "2") (pinfunction "S_2") (pintype "passive"))
    )
    (net (code "64") (name "Net-(Qir-G)") (class "Default")
      (node (ref "Porte ET") (pin "5") (pinfunction "5_5") (pintype "passive"))
      (node (ref "Qir") (pin "1") (pinfunction "G_1") (pintype "passive"))
    )
    (net (code "65") (name "Net-(QirOFF-D)") (class "Default")
      (node (ref "QirOFF") (pin "3") (pinfunction "D_3") (pintype "passive"))
      (node (ref "QirON") (pin "3") (pinfunction "D_3") (pintype "passive"))
      (node (ref "Rsave") (pin "1") (pinfunction "1_1") (pintype "passive"))
    )
    (net (code "66") (name "Net-(RledIR-TAP)") (class "Default")
      (node (ref "RledIR") (pin "2") (pinfunction "TAP_2") (pintype "passive"))
      (node (ref "Rsave") (pin "2") (pinfunction "2_2") (pintype "passive"))
    )
    (net (code "67") (name "Net-(RledIR-TOP)") (class "Default")
      (node (ref "DIR") (pin "2") (pinfunction "2_2") (pintype "passive"))
      (node (ref "RledIR") (pin "1") (pinfunction "TOP_1") (pintype "passive"))
    )
    (net (code "68") (name "Net-(Rset33a-Pad1)") (class "Default")
      (node (ref "Rset33a") (pin "1") (pinfunction "1_1") (pintype "passive"))
      (node (ref "Rset33b") (pin "2") (pinfunction "2_2") (pintype "passive"))
    )
    (net (code "69") (name "Net-(Rset33b-Pad1)") (class "Default")
      (node (ref "Rset33b") (pin "1") (pinfunction "1_1") (pintype "passive"))
      (node (ref "Rset33c") (pin "2") (pinfunction "2_2") (pintype "passive"))
    )
    (net (code "70") (name "Net-(Rset455a-Pad1)") (class "Default")
      (node (ref "Rset455a") (pin "1") (pinfunction "1_1") (pintype "passive"))
      (node (ref "Rset455b") (pin "2") (pinfunction "2_2") (pintype "passive"))
    )
    (net (code "71") (name "Net-(Rset455b-Pad1)") (class "Default")
      (node (ref "Rset455b") (pin "1") (pinfunction "1_1") (pintype "passive"))
      (node (ref "Rset455c") (pin "2") (pinfunction "2_2") (pintype "passive"))
    )
    (net (code "72") (name "Net-(Rset455c-Pad1)") (class "Default")
      (node (ref "Rset455c") (pin "1") (pinfunction "1_1") (pintype "passive"))
      (node (ref "Rset455d") (pin "2") (pinfunction "2_2") (pintype "passive"))
    )
    (net (code "73") (name "Net-(Rsynchro-Pad1)") (class "Default")
      (node (ref "Rsynchro") (pin "1") (pinfunction "1_1") (pintype "passive"))
      (node (ref "SYNCHRO") (pin "1") (pinfunction "1_1") (pintype "passive"))
    )
    (net (code "74") (name "Net-(Umot-OUT1)") (class "Default")
      (node (ref "MOTEUR") (pin "1") (pinfunction "1_1") (pintype "passive"))
      (node (ref "Umot") (pin "1") (pinfunction "OUT1_1") (pintype "output"))
    )
    (net (code "75") (name "Net-(Umot-OUT2)") (class "Default")
      (node (ref "MOTEUR") (pin "2") (pinfunction "2_2") (pintype "passive"))
      (node (ref "Umot") (pin "7") (pinfunction "OUT2_7") (pintype "output"))
    )
    (net (code "76") (name "Net-(Upic-C2RX{slash}RG0)") (class "Default")
      (node (ref "Interrupteur") (pin "1") (pinfunction "1_1") (pintype "passive"))
      (node (ref "RintPu") (pin "2") (pinfunction "2_2") (pintype "passive"))
      (node (ref "Upic") (pin "75") (pinfunction "C2RX/RG0_75") (pintype "bidirectional"))
    )
    (net (code "77") (name "Net-(Upic-C2TX{slash}RG1)") (class "Default")
      (node (ref "Interrupteur") (pin "2") (pinfunction "2_2") (pintype "passive"))
      (node (ref "RintPd") (pin "1") (pinfunction "1_1") (pintype "passive"))
      (node (ref "Upic") (pin "74") (pinfunction "C2TX/RG1_74") (pintype "bidirectional"))
    )
    (net (code "78") (name "Net-(Upic-EMUC3{slash}SCK1{slash}INT0{slash}RF6)") (class "Default")
      (node (ref "Csynchro") (pin "2") (pinfunction "2_2") (pintype "passive"))
      (node (ref "Rsynchro") (pin "2") (pinfunction "2_2") (pintype "passive"))
      (node (ref "Upic") (pin "43") (pinfunction "EMUD3/SDO1/RF8_43") (pintype "bidirectional"))
      (node (ref "Upic") (pin "45") (pinfunction "EMUC3/SCK1/INT0/RF6_45") (pintype "bidirectional"))
    )
    (net (code "79") (name "VCC") (class "Default")
      (node (ref "ALIM") (pin "2") (pinfunction "B2_2") (pintype "passive"))
      (node (ref "Cin") (pin "2") (pinfunction "2_2") (pintype "passive"))
      (node (ref "Cin2") (pin "2") (pinfunction "2_2") (pintype "passive"))
      (node (ref "Cmot") (pin "2") (pinfunction "2_2") (pintype "passive"))
      (node (ref "Umot") (pin "2") (pinfunction "VCC_2") (pintype "power_in"))
      (node (ref "Umot") (pin "3") (pinfunction "VCC_3") (pintype "power_in"))
      (node (ref "Umot") (pin "6") (pinfunction "VREF_6") (pintype "bidirectional"))
      (node (ref "Ureg") (pin "1") (pinfunction "IN_1") (pintype "power_in"))
    )
    (net (code "80") (name "VDD_RC1240") (class "Default")
      (node (ref "RC1240") (pin "11") (pinfunction "VDD_11") (pintype "passive"))
      (node (ref "RC1240") (pin "2") (pinfunction "CTS/RXTX/RXEN_2") (pintype "passive"))
      (node (ref "RC1240") (pin "3") (pinfunction "RTX/TXEN_3") (pintype "passive"))
    )
    (net (code "81") (name "Vdd") (class "Default")
      (node (ref "Ccod") (pin "2") (pinfunction "2_2") (pintype "passive"))
      (node (ref "Cd33") (pin "2") (pinfunction "2_2") (pintype "passive"))
      (node (ref "Cdpic1") (pin "1") (pinfunction "1_1") (pintype "passive"))
      (node (ref "Cdpic2") (pin "1") (pinfunction "1_1") (pintype "passive"))
      (node (ref "Cdpic3") (pin "1") (pinfunction "1_1") (pintype "passive"))
      (node (ref "Cdpic4") (pin "1") (pinfunction "1_1") (pintype "passive"))
      (node (ref "Codeur") (pin "4") (pinfunction "4_4") (pintype "passive"))
      (node (ref "Cout") (pin "2") (pinfunction "2_2") (pintype "passive"))
      (node (ref "Cout2") (pin "2") (pinfunction "2_2") (pintype "passive"))
      (node (ref "DIR") (pin "1") (pinfunction "1_1") (pintype "passive"))
      (node (ref "ICSP") (pin "2") (pinfunction "2_2") (pintype "passive"))
      (node (ref "OSC3.3") (pin "1") (pinfunction "1_1") (pintype "passive"))
      (node (ref "OSC3.3") (pin "4") (pinfunction "4_4") (pintype "passive"))
      (node (ref "Porte ET") (pin "6") (pinfunction "6_6") (pintype "passive"))
      (node (ref "RC1240") (pin "12") (pinfunction "ON/OFF_12") (pintype "passive"))
      (node (ref "RC1240") (pin "13") (pinfunction "VCC_13") (pintype "passive"))
      (node (ref "Rd455") (pin "2") (pinfunction "2_2") (pintype "passive"))
      (node (ref "RdOR") (pin "2") (pinfunction "2_2") (pintype "passive"))
      (node (ref "RintPu") (pin "1") (pinfunction "1_1") (pintype "passive"))
      (node (ref "Rmclr") (pin "2") (pinfunction "2_2") (pintype "passive"))
      (node (ref "Rpbt1") (pin "2") (pinfunction "2_2") (pintype "passive"))
      (node (ref "Rqoff") (pin "2") (pinfunction "2_2") (pintype "passive"))
      (node (ref "Rset33a") (pin "2") (pinfunction "2_2") (pintype "passive"))
      (node (ref "Ru1rx") (pin "2") (pinfunction "2_2") (pintype "passive"))
      (node (ref "Ru1tx") (pin "2") (pinfunction "2_2") (pintype "passive"))
      (node (ref "Upic") (pin "12") (pinfunction "VDD_12") (pintype "power_in"))
      (node (ref "Upic") (pin "24") (pinfunction "VREF+/RA10_24") (pintype "bidirectional"))
      (node (ref "Upic") (pin "25") (pinfunction "AVDD_25") (pintype "power_in"))
      (node (ref "Upic") (pin "32") (pinfunction "VDD_32") (pintype "power_in"))
      (node (ref "Upic") (pin "48") (pinfunction "VDD_48") (pintype "power_in"))
      (node (ref "Upic") (pin "71") (pinfunction "VDD_71") (pintype "power_in"))
      (node (ref "Ureg") (pin "3") (pinfunction "OUT_3") (pintype "power_in"))
    )
    (net (code "82") (name "unconnected-(Antenne_433-Pad2)") (class "Default")
      (node (ref "Antenne_433") (pin "2") (pinfunction "2_2") (pintype "passive+no_connect"))
    )
    (net (code "83") (name "unconnected-(ICSP-Pad6)") (class "Default")
      (node (ref "ICSP") (pin "6") (pinfunction "6_6") (pintype "passive"))
    )
    (net (code "84") (name "unconnected-(OSC3.3-Pad5)") (class "Default")
      (node (ref "OSC3.3") (pin "5") (pinfunction "5_5") (pintype "passive"))
    )
    (net (code "85") (name "unconnected-(Porte ET-Pad4)") (class "Default")
      (node (ref "Porte ET") (pin "4") (pinfunction "4_4") (pintype "passive"))
    )
    (net (code "86") (name "unconnected-(RC1240---Pad15)") (class "Default")
      (node (ref "RC1240") (pin "15") (pinfunction "-_15") (pintype "passive+no_connect"))
    )
    (net (code "87") (name "unconnected-(RC1240---Pad16)") (class "Default")
      (node (ref "RC1240") (pin "16") (pinfunction "-_16") (pintype "passive+no_connect"))
    )
    (net (code "88") (name "unconnected-(RC1240---Pad17)") (class "Default")
      (node (ref "RC1240") (pin "17") (pinfunction "-_17") (pintype "passive+no_connect"))
    )
    (net (code "89") (name "unconnected-(RC1240---Pad18)") (class "Default")
      (node (ref "RC1240") (pin "18") (pinfunction "-_18") (pintype "passive+no_connect"))
    )
    (net (code "90") (name "unconnected-(RC1240---Pad19)") (class "Default")
      (node (ref "RC1240") (pin "19") (pinfunction "-_19") (pintype "passive+no_connect"))
    )
    (net (code "91") (name "unconnected-(RC1240---Pad20)") (class "Default")
      (node (ref "RC1240") (pin "20") (pinfunction "-_20") (pintype "passive+no_connect"))
    )
    (net (code "92") (name "unconnected-(RC1240---Pad21)") (class "Default")
      (node (ref "RC1240") (pin "21") (pinfunction "-_21") (pintype "passive+no_connect"))
    )
    (net (code "93") (name "unconnected-(RC1240---Pad25)") (class "Default")
      (node (ref "RC1240") (pin "25") (pinfunction "-_25") (pintype "passive+no_connect"))
    )
    (net (code "94") (name "unconnected-(RC1240---Pad26)") (class "Default")
      (node (ref "RC1240") (pin "26") (pinfunction "-_26") (pintype "passive+no_connect"))
    )
    (net (code "95") (name "unconnected-(RC1240---Pad27)") (class "Default")
      (node (ref "RC1240") (pin "27") (pinfunction "-_27") (pintype "passive+no_connect"))
    )
    (net (code "96") (name "unconnected-(RC1240---Pad28)") (class "Default")
      (node (ref "RC1240") (pin "28") (pinfunction "-_28") (pintype "passive+no_connect"))
    )
    (net (code "97") (name "unconnected-(RC1240---Pad29)") (class "Default")
      (node (ref "RC1240") (pin "29") (pinfunction "-_29") (pintype "passive+no_connect"))
    )
    (net (code "98") (name "unconnected-(RC1240---Pad30)") (class "Default")
      (node (ref "RC1240") (pin "30") (pinfunction "-_30") (pintype "passive+no_connect"))
    )
    (net (code "99") (name "unconnected-(RC1240-LNA_EN-Pad24)") (class "Default")
      (node (ref "RC1240") (pin "24") (pinfunction "LNA_EN_24") (pintype "passive+no_connect"))
    )
    (net (code "100") (name "unconnected-(RC1240-PA_EN-Pad23)") (class "Default")
      (node (ref "RC1240") (pin "23") (pinfunction "PA_EN_23") (pintype "passive+no_connect"))
    )
    (net (code "101") (name "unconnected-(RledIR-BOT-Pad3)") (class "Default")
      (node (ref "RledIR") (pin "3") (pinfunction "BOT_3") (pintype "passive"))
    )
    (net (code "102") (name "unconnected-(Upic-AN6{slash}OCFA{slash}RB6-Pad21)") (class "Default")
      (node (ref "Upic") (pin "21") (pinfunction "AN6/OCFA/RB6_21") (pintype "bidirectional+no_connect"))
    )
    (net (code "103") (name "unconnected-(Upic-AN7{slash}RB7-Pad22)") (class "Default")
      (node (ref "Upic") (pin "22") (pinfunction "AN7/RB7_22") (pintype "bidirectional+no_connect"))
    )
    (net (code "104") (name "unconnected-(Upic-EMUC1{slash}SOSCO{slash}T1CK{slash}CN0{slash}RC14-Pad60)") (class "Default")
      (node (ref "Upic") (pin "60") (pinfunction "EMUC1/SOSCO/T1CK/CN0/RC14_60") (pintype "bidirectional+no_connect"))
    )
    (net (code "105") (name "unconnected-(Upic-EMUD1{slash}SOSCI{slash}CN1{slash}RC13-Pad59)") (class "Default")
      (node (ref "Upic") (pin "59") (pinfunction "EMUD1/SOSCI/CN1/RC13_59") (pintype "bidirectional+no_connect"))
    )
    (net (code "106") (name "unconnected-(Upic-EMUD2{slash}OC2{slash}RD1-Pad61)") (class "Default")
      (node (ref "Upic") (pin "61") (pinfunction "EMUD2/OC2/RD1_61") (pintype "bidirectional+no_connect"))
    )
    (net (code "107") (name "unconnected-(Upic-OC3{slash}RD2-Pad62)") (class "Default")
      (node (ref "Upic") (pin "62") (pinfunction "OC3/RD2_62") (pintype "bidirectional+no_connect"))
    )
    (net (code "108") (name "unconnected-(Upic-OC4{slash}RD3-Pad63)") (class "Default")
      (node (ref "Upic") (pin "63") (pinfunction "OC4/RD3_63") (pintype "bidirectional+no_connect"))
    )
    (net (code "109") (name "unconnected-(Upic-OC5{slash}CN13{slash}RD4-Pad66)") (class "Default")
      (node (ref "Upic") (pin "66") (pinfunction "OC5/CN13/RD4_66") (pintype "bidirectional"))
    )
    (net (code "110") (name "unconnected-(Upic-OC6{slash}CN14{slash}RD5-Pad67)") (class "Default")
      (node (ref "Upic") (pin "67") (pinfunction "OC6/CN14/RD5_67") (pintype "bidirectional"))
    )
    (net (code "111") (name "unconnected-(Upic-OC7{slash}CN15{slash}RD6-Pad68)") (class "Default")
      (node (ref "Upic") (pin "68") (pinfunction "OC7/CN15/RD6_68") (pintype "bidirectional"))
    )
    (net (code "112") (name "unconnected-(Upic-OC8{slash}UPDN{slash}CN16{slash}RD7-Pad69)") (class "Default")
      (node (ref "Upic") (pin "69") (pinfunction "OC8/UPDN/CN16/RD7_69") (pintype "bidirectional"))
    )
    (net (code "113") (name "unconnected-(Upic-PWM3H{slash}RE5-Pad1)") (class "Default")
      (node (ref "Upic") (pin "1") (pinfunction "PWM3H/RE5_1") (pintype "bidirectional"))
    )
    (net (code "114") (name "unconnected-(Upic-PWM3L{slash}RE4-Pad80)") (class "Default")
      (node (ref "Upic") (pin "80") (pinfunction "PWM3L/RE4_80") (pintype "bidirectional"))
    )
    (net (code "115") (name "unconnected-(Upic-SDI1{slash}RF7-Pad44)") (class "Default")
      (node (ref "Upic") (pin "44") (pinfunction "SDI1/RF7_44") (pintype "bidirectional+no_connect"))
    )
    (net (code "116") (name "unconnected-(Upic-T2CK{slash}RC1-Pad4)") (class "Default")
      (node (ref "Upic") (pin "4") (pinfunction "T2CK/RC1_4") (pintype "bidirectional+no_connect"))
    )
    (net (code "117") (name "unconnected-(Upic-T4CK{slash}RC3-Pad5)") (class "Default")
      (node (ref "Upic") (pin "5") (pinfunction "T4CK/RC3_5") (pintype "bidirectional+no_connect"))
    )
  )
)
